# 5_Limit_Switches.net
KiCad netlist of a schematic drawn in Altium Designer
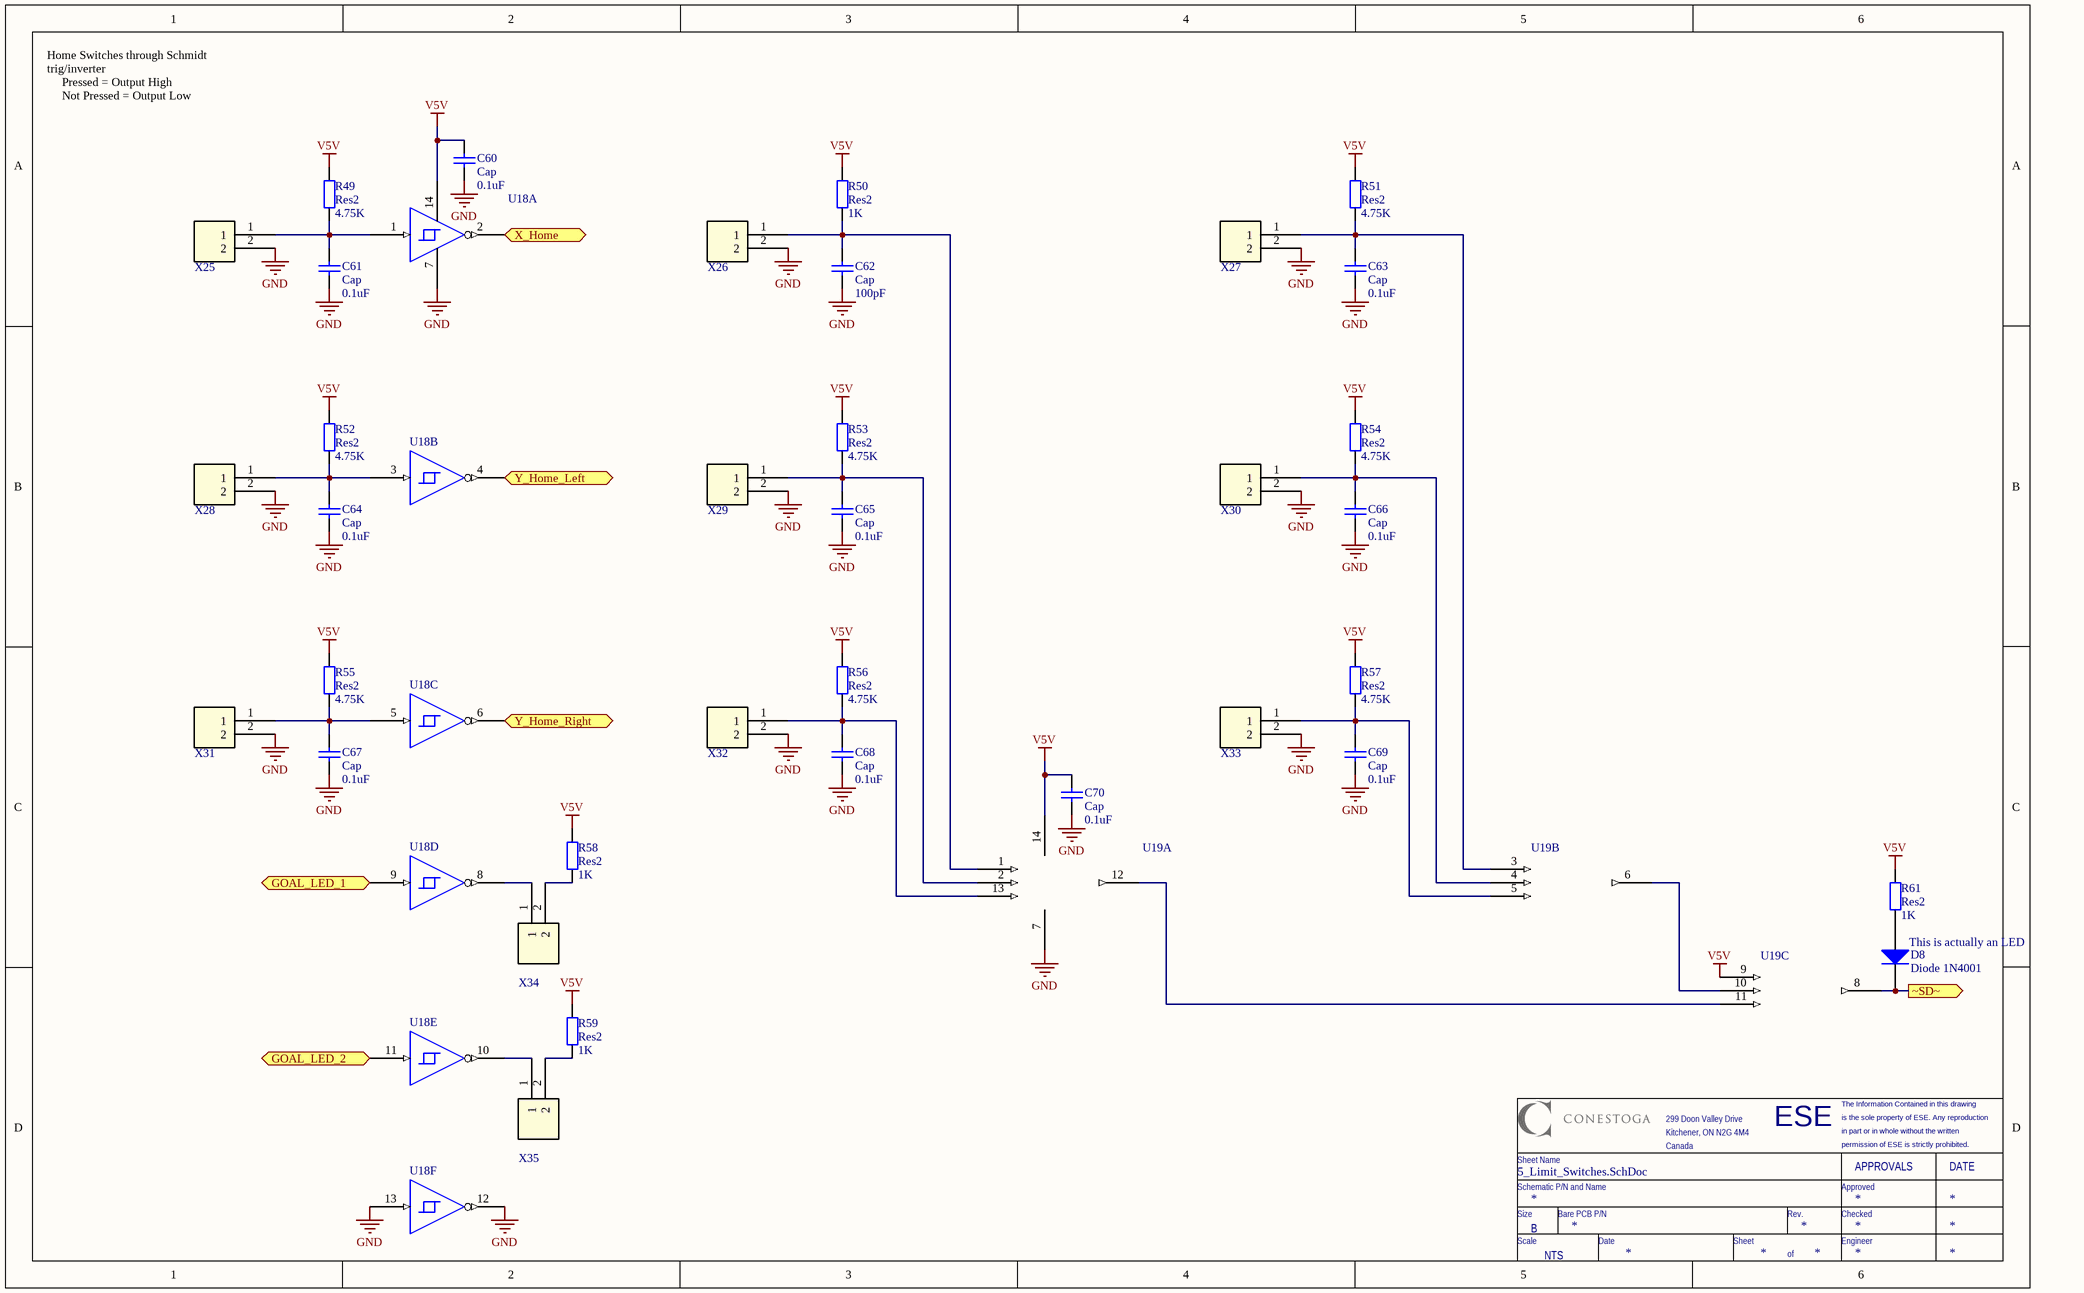
[diagram p0: 5_Limit_Switches.SchDoc]

(export (version "E")
  (design (tool "Eeschema 10.0.6"))
  (components
    (comp (ref "C60")
      (value "Cap")
      (footprint "RAD-0.3")
      (description "Capacitor")
      (fields (field (name "ALTIUM_VALUE") "0.1uF") (field (name "PUBLISHER") "Altium Limited"))
      (libsource (lib "Miscellaneous Devices") (part "Cap"))
    )
    (comp (ref "C61")
      (value "Cap")
      (footprint "RAD-0.3")
      (description "Capacitor")
      (fields (field (name "ALTIUM_VALUE") "0.1uF") (field (name "PUBLISHER") "Altium Limited"))
      (libsource (lib "Miscellaneous Devices") (part "Cap"))
    )
    (comp (ref "C62")
      (value "Cap")
      (footprint "RAD-0.3")
      (description "Capacitor")
      (fields (field (name "ALTIUM_VALUE") "100pF") (field (name "PUBLISHER") "Altium Limited"))
      (libsource (lib "Miscellaneous Devices") (part "Cap"))
    )
    (comp (ref "C63")
      (value "Cap")
      (footprint "RAD-0.3")
      (description "Capacitor")
      (fields (field (name "ALTIUM_VALUE") "0.1uF") (field (name "PUBLISHER") "Altium Limited"))
      (libsource (lib "Miscellaneous Devices") (part "Cap"))
    )
    (comp (ref "C64")
      (value "Cap")
      (footprint "RAD-0.3")
      (description "Capacitor")
      (fields (field (name "ALTIUM_VALUE") "0.1uF") (field (name "PUBLISHER") "Altium Limited"))
      (libsource (lib "Miscellaneous Devices") (part "Cap"))
    )
    (comp (ref "C65")
      (value "Cap")
      (footprint "RAD-0.3")
      (description "Capacitor")
      (fields (field (name "ALTIUM_VALUE") "0.1uF") (field (name "PUBLISHER") "Altium Limited"))
      (libsource (lib "Miscellaneous Devices") (part "Cap"))
    )
    (comp (ref "C66")
      (value "Cap")
      (footprint "RAD-0.3")
      (description "Capacitor")
      (fields (field (name "ALTIUM_VALUE") "0.1uF") (field (name "PUBLISHER") "Altium Limited"))
      (libsource (lib "Miscellaneous Devices") (part "Cap"))
    )
    (comp (ref "C67")
      (value "Cap")
      (footprint "RAD-0.3")
      (description "Capacitor")
      (fields (field (name "ALTIUM_VALUE") "0.1uF") (field (name "PUBLISHER") "Altium Limited"))
      (libsource (lib "Miscellaneous Devices") (part "Cap"))
    )
    (comp (ref "C68")
      (value "Cap")
      (footprint "RAD-0.3")
      (description "Capacitor")
      (fields (field (name "ALTIUM_VALUE") "0.1uF") (field (name "PUBLISHER") "Altium Limited"))
      (libsource (lib "Miscellaneous Devices") (part "Cap"))
    )
    (comp (ref "C69")
      (value "Cap")
      (footprint "RAD-0.3")
      (description "Capacitor")
      (fields (field (name "ALTIUM_VALUE") "0.1uF") (field (name "PUBLISHER") "Altium Limited"))
      (libsource (lib "Miscellaneous Devices") (part "Cap"))
    )
    (comp (ref "C70")
      (value "Cap")
      (footprint "RAD-0.3")
      (description "Capacitor")
      (fields (field (name "ALTIUM_VALUE") "0.1uF") (field (name "PUBLISHER") "Altium Limited"))
      (libsource (lib "Miscellaneous Devices") (part "Cap"))
    )
    (comp (ref "D8")
      (value "Diode 1N4001")
      (footprint "DO-41")
      (description "1 Amp General Purpose Rectifier")
      (fields (field (name "PUBLISHER") "Altium Limited"))
      (libsource (lib "Miscellaneous Devices") (part "Diode 1N4001"))
    )
    (comp (ref "R49")
      (value "Res2")
      (footprint "AXIAL-0.4")
      (description "Resistor")
      (fields (field (name "ALTIUM_VALUE") "4.75K") (field (name "PUBLISHER") "Altium Limited"))
      (libsource (lib "Miscellaneous Devices") (part "Res2"))
    )
    (comp (ref "R50")
      (value "Res2")
      (footprint "AXIAL-0.4")
      (description "Resistor")
      (fields (field (name "ALTIUM_VALUE") "1K") (field (name "PUBLISHER") "Altium Limited"))
      (libsource (lib "Miscellaneous Devices") (part "Res2"))
    )
    (comp (ref "R51")
      (value "Res2")
      (footprint "AXIAL-0.4")
      (description "Resistor")
      (fields (field (name "ALTIUM_VALUE") "4.75K") (field (name "PUBLISHER") "Altium Limited"))
      (libsource (lib "Miscellaneous Devices") (part "Res2"))
    )
    (comp (ref "R52")
      (value "Res2")
      (footprint "AXIAL-0.4")
      (description "Resistor")
      (fields (field (name "ALTIUM_VALUE") "4.75K") (field (name "PUBLISHER") "Altium Limited"))
      (libsource (lib "Miscellaneous Devices") (part "Res2"))
    )
    (comp (ref "R53")
      (value "Res2")
      (footprint "AXIAL-0.4")
      (description "Resistor")
      (fields (field (name "ALTIUM_VALUE") "4.75K") (field (name "PUBLISHER") "Altium Limited"))
      (libsource (lib "Miscellaneous Devices") (part "Res2"))
    )
    (comp (ref "R54")
      (value "Res2")
      (footprint "AXIAL-0.4")
      (description "Resistor")
      (fields (field (name "ALTIUM_VALUE") "4.75K") (field (name "PUBLISHER") "Altium Limited"))
      (libsource (lib "Miscellaneous Devices") (part "Res2"))
    )
    (comp (ref "R55")
      (value "Res2")
      (footprint "AXIAL-0.4")
      (description "Resistor")
      (fields (field (name "ALTIUM_VALUE") "4.75K") (field (name "PUBLISHER") "Altium Limited"))
      (libsource (lib "Miscellaneous Devices") (part "Res2"))
    )
    (comp (ref "R56")
      (value "Res2")
      (footprint "AXIAL-0.4")
      (description "Resistor")
      (fields (field (name "ALTIUM_VALUE") "4.75K") (field (name "PUBLISHER") "Altium Limited"))
      (libsource (lib "Miscellaneous Devices") (part "Res2"))
    )
    (comp (ref "R57")
      (value "Res2")
      (footprint "AXIAL-0.4")
      (description "Resistor")
      (fields (field (name "ALTIUM_VALUE") "4.75K") (field (name "PUBLISHER") "Altium Limited"))
      (libsource (lib "Miscellaneous Devices") (part "Res2"))
    )
    (comp (ref "R58")
      (value "Res2")
      (footprint "AXIAL-0.4")
      (description "Resistor")
      (fields (field (name "ALTIUM_VALUE") "1K") (field (name "PUBLISHER") "Altium Limited"))
      (libsource (lib "Miscellaneous Devices") (part "Res2"))
    )
    (comp (ref "R59")
      (value "Res2")
      (footprint "AXIAL-0.4")
      (description "Resistor")
      (fields (field (name "ALTIUM_VALUE") "1K") (field (name "PUBLISHER") "Altium Limited"))
      (libsource (lib "Miscellaneous Devices") (part "Res2"))
    )
    (comp (ref "R61")
      (value "Res2")
      (footprint "AXIAL-0.4")
      (description "Resistor")
      (fields (field (name "ALTIUM_VALUE") "1K") (field (name "PUBLISHER") "Altium Limited"))
      (libsource (lib "Miscellaneous Devices") (part "Res2"))
    )
    (comp (ref "U18")
      (value "IC HEX SCHMITT-TRIG INV 14-DIP")
      (footprint "14-DIP")
      (fields
        (field (name "DIGI-KEY_PART_NUMBER") "296-4368-5-ND")
        (field (name "MANUFACTUER_PART_NUMBER") "SN74ACT14N")
        (field (name "MANUFACTURER") "Texas Instruments")
      )
      (libsource (lib "thomas_lib") (part "IC HEX SCHMITT-TRIG INV 14-DIP"))
    )
    (comp (ref "U19")
      (value "IC GATE AND 3CH 3-INP 14DIP")
      (footprint "14-DIP")
      (fields
        (field (name "DIGI-KEY_PART_NUMBER") "296-8217-5-ND")
        (field (name "MANUFACTUER_PART_NUMBER") "SN74HC11N")
        (field (name "MANUFACTURER") "Texas Instruments")
      )
      (libsource (lib "thomas_lib") (part "IC GATE AND 3CH 3-INP 14DIP"))
    )
    (comp (ref "X25")
      (value "TERM BLOCK HDR 2POS VERT 3.5MM")
      (footprint "WR-TBL-3211 2")
      (fields
        (field (name "DIGIKEY_PART_NUMBER") "732-2763-ND")
        (field (name "MANUFACTURER_PART_NUMBER") "691321100002")
        (field (name "MANUFACTURER") "Wurth Electronics Inc")
      )
      (libsource (lib "thomas_lib") (part "TERM BLOCK HDR 2POS VERT 3.5MM"))
    )
    (comp (ref "X26")
      (value "TERM BLOCK HDR 2POS VERT 3.5MM")
      (footprint "WR-TBL-3211 2")
      (fields
        (field (name "DIGIKEY_PART_NUMBER") "732-2763-ND")
        (field (name "MANUFACTURER_PART_NUMBER") "691321100002")
        (field (name "MANUFACTURER") "Wurth Electronics Inc")
      )
      (libsource (lib "thomas_lib") (part "TERM BLOCK HDR 2POS VERT 3.5MM"))
    )
    (comp (ref "X27")
      (value "TERM BLOCK HDR 2POS VERT 3.5MM")
      (footprint "WR-TBL-3211 2")
      (fields
        (field (name "DIGIKEY_PART_NUMBER") "732-2763-ND")
        (field (name "MANUFACTURER_PART_NUMBER") "691321100002")
        (field (name "MANUFACTURER") "Wurth Electronics Inc")
      )
      (libsource (lib "thomas_lib") (part "TERM BLOCK HDR 2POS VERT 3.5MM"))
    )
    (comp (ref "X28")
      (value "TERM BLOCK HDR 2POS VERT 3.5MM")
      (footprint "WR-TBL-3211 2")
      (fields
        (field (name "DIGIKEY_PART_NUMBER") "732-2763-ND")
        (field (name "MANUFACTURER_PART_NUMBER") "691321100002")
        (field (name "MANUFACTURER") "Wurth Electronics Inc")
      )
      (libsource (lib "thomas_lib") (part "TERM BLOCK HDR 2POS VERT 3.5MM"))
    )
    (comp (ref "X29")
      (value "TERM BLOCK HDR 2POS VERT 3.5MM")
      (footprint "WR-TBL-3211 2")
      (fields
        (field (name "DIGIKEY_PART_NUMBER") "732-2763-ND")
        (field (name "MANUFACTURER_PART_NUMBER") "691321100002")
        (field (name "MANUFACTURER") "Wurth Electronics Inc")
      )
      (libsource (lib "thomas_lib") (part "TERM BLOCK HDR 2POS VERT 3.5MM"))
    )
    (comp (ref "X30")
      (value "TERM BLOCK HDR 2POS VERT 3.5MM")
      (footprint "WR-TBL-3211 2")
      (fields
        (field (name "DIGIKEY_PART_NUMBER") "732-2763-ND")
        (field (name "MANUFACTURER_PART_NUMBER") "691321100002")
        (field (name "MANUFACTURER") "Wurth Electronics Inc")
      )
      (libsource (lib "thomas_lib") (part "TERM BLOCK HDR 2POS VERT 3.5MM"))
    )
    (comp (ref "X31")
      (value "TERM BLOCK HDR 2POS VERT 3.5MM")
      (footprint "WR-TBL-3211 2")
      (fields
        (field (name "DIGIKEY_PART_NUMBER") "732-2763-ND")
        (field (name "MANUFACTURER_PART_NUMBER") "691321100002")
        (field (name "MANUFACTURER") "Wurth Electronics Inc")
      )
      (libsource (lib "thomas_lib") (part "TERM BLOCK HDR 2POS VERT 3.5MM"))
    )
    (comp (ref "X32")
      (value "TERM BLOCK HDR 2POS VERT 3.5MM")
      (footprint "WR-TBL-3211 2")
      (fields
        (field (name "DIGIKEY_PART_NUMBER") "732-2763-ND")
        (field (name "MANUFACTURER_PART_NUMBER") "691321100002")
        (field (name "MANUFACTURER") "Wurth Electronics Inc")
      )
      (libsource (lib "thomas_lib") (part "TERM BLOCK HDR 2POS VERT 3.5MM"))
    )
    (comp (ref "X33")
      (value "TERM BLOCK HDR 2POS VERT 3.5MM")
      (footprint "WR-TBL-3211 2")
      (fields
        (field (name "DIGIKEY_PART_NUMBER") "732-2763-ND")
        (field (name "MANUFACTURER_PART_NUMBER") "691321100002")
        (field (name "MANUFACTURER") "Wurth Electronics Inc")
      )
      (libsource (lib "thomas_lib") (part "TERM BLOCK HDR 2POS VERT 3.5MM"))
    )
    (comp (ref "X34")
      (value "TERM BLOCK HDR 2POS VERT 3.5MM")
      (footprint "WR-TBL-3211 2")
      (fields
        (field (name "DIGIKEY_PART_NUMBER") "732-2763-ND")
        (field (name "MANUFACTURER_PART_NUMBER") "691321100002")
        (field (name "MANUFACTURER") "Wurth Electronics Inc")
      )
      (libsource (lib "") (part "TERM BLOCK HDR 2POS VERT 3.5MM_1"))
    )
    (comp (ref "X35")
      (value "TERM BLOCK HDR 2POS VERT 3.5MM")
      (footprint "WR-TBL-3211 2")
      (fields
        (field (name "DIGIKEY_PART_NUMBER") "732-2763-ND")
        (field (name "MANUFACTURER_PART_NUMBER") "691321100002")
        (field (name "MANUFACTURER") "Wurth Electronics Inc")
      )
      (libsource (lib "") (part "TERM BLOCK HDR 2POS VERT 3.5MM_1"))
    )
  )
  (nets
    (net (code "1") (name "/GOAL_LED_1") (class "Default")
      (node (ref "U18") (pin "9") (pinfunction "A_9") (pintype "input"))
    )
    (net (code "2") (name "/GOAL_LED_2") (class "Default")
      (node (ref "U18") (pin "11") (pinfunction "A_11") (pintype "input"))
    )
    (net (code "3") (name "/X_Home") (class "Default")
      (node (ref "U18") (pin "2") (pinfunction "Y_2") (pintype "output"))
    )
    (net (code "4") (name "/Y_Home_Left") (class "Default")
      (node (ref "U18") (pin "4") (pinfunction "Y_4") (pintype "output"))
    )
    (net (code "5") (name "/Y_Home_Right") (class "Default")
      (node (ref "U18") (pin "6") (pinfunction "Y_6") (pintype "output"))
    )
    (net (code "6") (name "/~SD~") (class "Default")
      (node (ref "D8") (pin "2") (pinfunction "K_2") (pintype "passive"))
      (node (ref "U19") (pin "8") (pinfunction "3Y_8") (pintype "output"))
    )
    (net (code "7") (name "GND") (class "Default")
      (node (ref "C60") (pin "1") (pinfunction "1_1") (pintype "passive"))
      (node (ref "C61") (pin "1") (pinfunction "1_1") (pintype "passive"))
      (node (ref "C62") (pin "1") (pinfunction "1_1") (pintype "passive"))
      (node (ref "C63") (pin "1") (pinfunction "1_1") (pintype "passive"))
      (node (ref "C64") (pin "1") (pinfunction "1_1") (pintype "passive"))
      (node (ref "C65") (pin "1") (pinfunction "1_1") (pintype "passive"))
      (node (ref "C66") (pin "1") (pinfunction "1_1") (pintype "passive"))
      (node (ref "C67") (pin "1") (pinfunction "1_1") (pintype "passive"))
      (node (ref "C68") (pin "1") (pinfunction "1_1") (pintype "passive"))
      (node (ref "C69") (pin "1") (pinfunction "1_1") (pintype "passive"))
      (node (ref "C70") (pin "1") (pinfunction "1_1") (pintype "passive"))
      (node (ref "U18") (pin "12") (pinfunction "Y_12") (pintype "output"))
      (node (ref "U18") (pin "13") (pinfunction "A_13") (pintype "input"))
      (node (ref "U18") (pin "7") (pinfunction "GND_POWER_7") (pintype "power_in"))
      (node (ref "U19") (pin "7") (pinfunction "GND_POWER_7") (pintype "power_in"))
      (node (ref "X25") (pin "2") (pinfunction "2_2") (pintype "passive"))
      (node (ref "X26") (pin "2") (pinfunction "2_2") (pintype "passive"))
      (node (ref "X27") (pin "2") (pinfunction "2_2") (pintype "passive"))
      (node (ref "X28") (pin "2") (pinfunction "2_2") (pintype "passive"))
      (node (ref "X29") (pin "2") (pinfunction "2_2") (pintype "passive"))
      (node (ref "X30") (pin "2") (pinfunction "2_2") (pintype "passive"))
      (node (ref "X31") (pin "2") (pinfunction "2_2") (pintype "passive"))
      (node (ref "X32") (pin "2") (pinfunction "2_2") (pintype "passive"))
      (node (ref "X33") (pin "2") (pinfunction "2_2") (pintype "passive"))
    )
    (net (code "8") (name "Net-(D8-A)") (class "Default")
      (node (ref "D8") (pin "1") (pinfunction "A_1") (pintype "passive"))
      (node (ref "R61") (pin "1") (pinfunction "1_1") (pintype "passive"))
    )
    (net (code "9") (name "Net-(R58-Pad1)") (class "Default")
      (node (ref "R58") (pin "1") (pinfunction "1_1") (pintype "passive"))
      (node (ref "X34") (pin "2") (pinfunction "2_2") (pintype "passive"))
    )
    (net (code "10") (name "Net-(R59-Pad1)") (class "Default")
      (node (ref "R59") (pin "1") (pinfunction "1_1") (pintype "passive"))
      (node (ref "X35") (pin "2") (pinfunction "2_2") (pintype "passive"))
    )
    (net (code "11") (name "Net-(U18A-A)") (class "Default")
      (node (ref "C61") (pin "2") (pinfunction "2_2") (pintype "passive"))
      (node (ref "R49") (pin "1") (pinfunction "1_1") (pintype "passive"))
      (node (ref "U18") (pin "1") (pinfunction "A_1") (pintype "input"))
      (node (ref "X25") (pin "1") (pinfunction "1_1") (pintype "passive"))
    )
    (net (code "12") (name "Net-(U18B-A)") (class "Default")
      (node (ref "C64") (pin "2") (pinfunction "2_2") (pintype "passive"))
      (node (ref "R52") (pin "1") (pinfunction "1_1") (pintype "passive"))
      (node (ref "U18") (pin "3") (pinfunction "A_3") (pintype "input"))
      (node (ref "X28") (pin "1") (pinfunction "1_1") (pintype "passive"))
    )
    (net (code "13") (name "Net-(U18C-A)") (class "Default")
      (node (ref "C67") (pin "2") (pinfunction "2_2") (pintype "passive"))
      (node (ref "R55") (pin "1") (pinfunction "1_1") (pintype "passive"))
      (node (ref "U18") (pin "5") (pinfunction "A_5") (pintype "input"))
      (node (ref "X31") (pin "1") (pinfunction "1_1") (pintype "passive"))
    )
    (net (code "14") (name "Net-(U18D-Y)") (class "Default")
      (node (ref "U18") (pin "8") (pinfunction "Y_8") (pintype "output"))
      (node (ref "X34") (pin "1") (pinfunction "1_1") (pintype "passive"))
    )
    (net (code "15") (name "Net-(U18E-Y)") (class "Default")
      (node (ref "U18") (pin "10") (pinfunction "Y_10") (pintype "output"))
      (node (ref "X35") (pin "1") (pinfunction "1_1") (pintype "passive"))
    )
    (net (code "16") (name "Net-(U19A-1A)") (class "Default")
      (node (ref "C62") (pin "2") (pinfunction "2_2") (pintype "passive"))
      (node (ref "R50") (pin "1") (pinfunction "1_1") (pintype "passive"))
      (node (ref "U19") (pin "1") (pinfunction "1A_1") (pintype "input"))
      (node (ref "X26") (pin "1") (pinfunction "1_1") (pintype "passive"))
    )
    (net (code "17") (name "Net-(U19A-1B)") (class "Default")
      (node (ref "C65") (pin "2") (pinfunction "2_2") (pintype "passive"))
      (node (ref "R53") (pin "1") (pinfunction "1_1") (pintype "passive"))
      (node (ref "U19") (pin "2") (pinfunction "1B_2") (pintype "input"))
      (node (ref "X29") (pin "1") (pinfunction "1_1") (pintype "passive"))
    )
    (net (code "18") (name "Net-(U19A-1C)") (class "Default")
      (node (ref "C68") (pin "2") (pinfunction "2_2") (pintype "passive"))
      (node (ref "R56") (pin "1") (pinfunction "1_1") (pintype "passive"))
      (node (ref "U19") (pin "13") (pinfunction "1C_13") (pintype "input"))
      (node (ref "X32") (pin "1") (pinfunction "1_1") (pintype "passive"))
    )
    (net (code "19") (name "Net-(U19A-1Y)") (class "Default")
      (node (ref "U19") (pin "11") (pinfunction "3C_11") (pintype "input"))
      (node (ref "U19") (pin "12") (pinfunction "1Y_12") (pintype "output"))
    )
    (net (code "20") (name "Net-(U19B-2A)") (class "Default")
      (node (ref "C63") (pin "2") (pinfunction "2_2") (pintype "passive"))
      (node (ref "R51") (pin "1") (pinfunction "1_1") (pintype "passive"))
      (node (ref "U19") (pin "3") (pinfunction "2A_3") (pintype "input"))
      (node (ref "X27") (pin "1") (pinfunction "1_1") (pintype "passive"))
    )
    (net (code "21") (name "Net-(U19B-2B)") (class "Default")
      (node (ref "C66") (pin "2") (pinfunction "2_2") (pintype "passive"))
      (node (ref "R54") (pin "1") (pinfunction "1_1") (pintype "passive"))
      (node (ref "U19") (pin "4") (pinfunction "2B_4") (pintype "input"))
      (node (ref "X30") (pin "1") (pinfunction "1_1") (pintype "passive"))
    )
    (net (code "22") (name "Net-(U19B-2C)") (class "Default")
      (node (ref "C69") (pin "2") (pinfunction "2_2") (pintype "passive"))
      (node (ref "R57") (pin "1") (pinfunction "1_1") (pintype "passive"))
      (node (ref "U19") (pin "5") (pinfunction "2C_5") (pintype "input"))
      (node (ref "X33") (pin "1") (pinfunction "1_1") (pintype "passive"))
    )
    (net (code "23") (name "Net-(U19B-2Y)") (class "Default")
      (node (ref "U19") (pin "10") (pinfunction "3B_10") (pintype "input"))
      (node (ref "U19") (pin "6") (pinfunction "2Y_6") (pintype "output"))
    )
    (net (code "24") (name "V5V") (class "Default")
      (node (ref "C60") (pin "2") (pinfunction "2_2") (pintype "passive"))
      (node (ref "C70") (pin "2") (pinfunction "2_2") (pintype "passive"))
      (node (ref "R49") (pin "2") (pinfunction "2_2") (pintype "passive"))
      (node (ref "R50") (pin "2") (pinfunction "2_2") (pintype "passive"))
      (node (ref "R51") (pin "2") (pinfunction "2_2") (pintype "passive"))
      (node (ref "R52") (pin "2") (pinfunction "2_2") (pintype "passive"))
      (node (ref "R53") (pin "2") (pinfunction "2_2") (pintype "passive"))
      (node (ref "R54") (pin "2") (pinfunction "2_2") (pintype "passive"))
      (node (ref "R55") (pin "2") (pinfunction "2_2") (pintype "passive"))
      (node (ref "R56") (pin "2") (pinfunction "2_2") (pintype "passive"))
      (node (ref "R57") (pin "2") (pinfunction "2_2") (pintype "passive"))
      (node (ref "R58") (pin "2") (pinfunction "2_2") (pintype "passive"))
      (node (ref "R59") (pin "2") (pinfunction "2_2") (pintype "passive"))
      (node (ref "R61") (pin "2") (pinfunction "2_2") (pintype "passive"))
      (node (ref "U18") (pin "14") (pinfunction "VCC_14") (pintype "power_in"))
      (node (ref "U19") (pin "14") (pinfunction "VCC_14") (pintype "power_in"))
      (node (ref "U19") (pin "9") (pinfunction "3A_9") (pintype "input"))
    )
  )
)
